# relogioContador.net
KiCad netlist of a schematic drawn in EAGLE
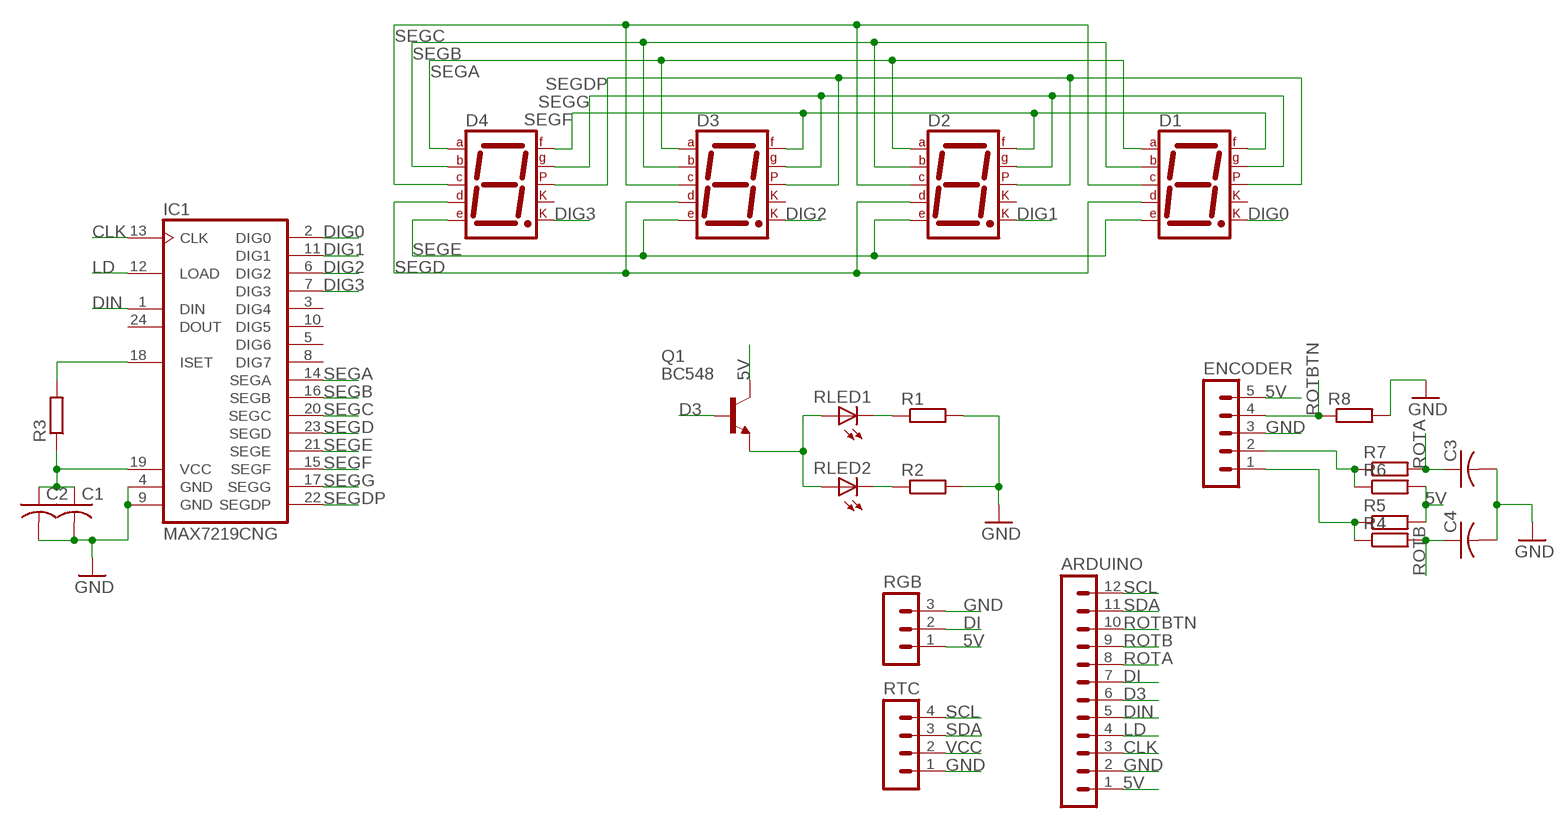
[diagram p0: schematic, sheet 1]

(export (version "E")
  (design (tool "Eeschema 10.0.6"))
  (components
    (comp (ref "ARDUINO")
      (value "MA12-1")
      (footprint "eagle-import:MA12-1")
      (libsource (lib "eagle-import") (part "MA12-1"))
    )
    (comp (ref "C1")
      (value "C-US050-025X075")
      (footprint "eagle-import:C050-025X075")
      (libsource (lib "eagle-import") (part "C-US050-025X075"))
    )
    (comp (ref "C2")
      (value "C-US050-025X075")
      (footprint "eagle-import:C050-025X075")
      (libsource (lib "eagle-import") (part "C-US050-025X075"))
    )
    (comp (ref "C3")
      (value "C-US050-025X075")
      (footprint "eagle-import:C050-025X075")
      (libsource (lib "eagle-import") (part "C-US050-025X075"))
    )
    (comp (ref "C4")
      (value "C-US050-025X075")
      (footprint "eagle-import:C050-025X075")
      (libsource (lib "eagle-import") (part "C-US050-025X075"))
    )
    (comp (ref "D1")
      (value "7SEG-CK")
      (footprint "eagle-import:7SEG-13")
      (libsource (lib "eagle-import") (part "7SEG-CK"))
    )
    (comp (ref "D2")
      (value "7SEG-CK")
      (footprint "eagle-import:7SEG-13")
      (libsource (lib "eagle-import") (part "7SEG-CK"))
    )
    (comp (ref "D3")
      (value "7SEG-CK")
      (footprint "eagle-import:7SEG-13")
      (libsource (lib "eagle-import") (part "7SEG-CK"))
    )
    (comp (ref "D4")
      (value "7SEG-CK")
      (footprint "eagle-import:7SEG-13")
      (libsource (lib "eagle-import") (part "7SEG-CK"))
    )
    (comp (ref "ENCODER")
      (value "MA05-1")
      (footprint "eagle-import:MA05-1")
      (libsource (lib "eagle-import") (part "MA05-1"))
    )
    (comp (ref "IC1")
      (value "MAX7219CNG")
      (footprint "eagle-import:DIL24-3")
      (fields (field (name "MF") "MAXIM"))
      (libsource (lib "eagle-import") (part "MAX7219CNG"))
    )
    (comp (ref "Q1")
      (value "BC548")
      (footprint "eagle-import:TO92-EBC")
      (libsource (lib "eagle-import") (part "BC548"))
    )
    (comp (ref "R1")
      (value "R-EU_0411/15")
      (footprint "eagle-import:0411_15")
      (libsource (lib "eagle-import") (part "R-EU_0411/15"))
    )
    (comp (ref "R2")
      (value "R-EU_0411/15")
      (footprint "eagle-import:0411_15")
      (libsource (lib "eagle-import") (part "R-EU_0411/15"))
    )
    (comp (ref "R3")
      (value "R-EU_0411/15")
      (footprint "eagle-import:0411_15")
      (libsource (lib "eagle-import") (part "R-EU_0411/15"))
    )
    (comp (ref "R4")
      (value "R-EU_0411/15")
      (footprint "eagle-import:0411_15")
      (libsource (lib "eagle-import") (part "R-EU_0411/15"))
    )
    (comp (ref "R5")
      (value "R-EU_0411/15")
      (footprint "eagle-import:0411_15")
      (libsource (lib "eagle-import") (part "R-EU_0411/15"))
    )
    (comp (ref "R6")
      (value "R-EU_0411/15")
      (footprint "eagle-import:0411_15")
      (libsource (lib "eagle-import") (part "R-EU_0411/15"))
    )
    (comp (ref "R7")
      (value "R-EU_0411/15")
      (footprint "eagle-import:0411_15")
      (libsource (lib "eagle-import") (part "R-EU_0411/15"))
    )
    (comp (ref "R8")
      (value "R-EU_0411/15")
      (footprint "eagle-import:0411_15")
      (libsource (lib "eagle-import") (part "R-EU_0411/15"))
    )
    (comp (ref "RGB")
      (value "MA03-1")
      (footprint "eagle-import:MA03-1")
      (libsource (lib "eagle-import") (part "MA03-1"))
    )
    (comp (ref "RLED1")
      (value "LED3MM")
      (footprint "eagle-import:LED3MM")
      (libsource (lib "eagle-import") (part "LED3MM"))
    )
    (comp (ref "RLED2")
      (value "LED3MM")
      (footprint "eagle-import:LED3MM")
      (libsource (lib "eagle-import") (part "LED3MM"))
    )
    (comp (ref "RTC")
      (value "MA04-1")
      (footprint "eagle-import:MA04-1")
      (libsource (lib "eagle-import") (part "MA04-1"))
    )
  )
  (nets
    (net (code "1") (name "/5V") (class "Default")
      (node (ref "ARDUINO") (pin "1") (pinfunction "1_1") (pintype "passive"))
      (node (ref "ENCODER") (pin "5") (pinfunction "5_5") (pintype "passive"))
      (node (ref "Q1") (pin "C") (pinfunction "C_C") (pintype "passive"))
      (node (ref "R5") (pin "2") (pinfunction "2_2") (pintype "passive"))
      (node (ref "R6") (pin "2") (pinfunction "2_2") (pintype "passive"))
      (node (ref "RGB") (pin "1") (pinfunction "1_1") (pintype "passive"))
    )
    (net (code "2") (name "/CLK") (class "Default")
      (node (ref "ARDUINO") (pin "3") (pinfunction "3_3") (pintype "passive"))
      (node (ref "IC1") (pin "13") (pinfunction "CLK_13") (pintype "input"))
    )
    (net (code "3") (name "/D3") (class "Default")
      (node (ref "ARDUINO") (pin "6") (pinfunction "6_6") (pintype "passive"))
      (node (ref "Q1") (pin "B") (pinfunction "B_B") (pintype "passive"))
    )
    (net (code "4") (name "/DI") (class "Default")
      (node (ref "ARDUINO") (pin "7") (pinfunction "7_7") (pintype "passive"))
      (node (ref "RGB") (pin "2") (pinfunction "2_2") (pintype "passive"))
    )
    (net (code "5") (name "/DIG0") (class "Default")
      (node (ref "D1") (pin "8") (pinfunction "CK2_8") (pintype "passive"))
      (node (ref "IC1") (pin "2") (pinfunction "DIG0_2") (pintype "output"))
    )
    (net (code "6") (name "/DIG1") (class "Default")
      (node (ref "D2") (pin "8") (pinfunction "CK2_8") (pintype "passive"))
      (node (ref "IC1") (pin "11") (pinfunction "DIG1_11") (pintype "output"))
    )
    (net (code "7") (name "/DIG2") (class "Default")
      (node (ref "D3") (pin "8") (pinfunction "CK2_8") (pintype "passive"))
      (node (ref "IC1") (pin "6") (pinfunction "DIG2_6") (pintype "output"))
    )
    (net (code "8") (name "/DIG3") (class "Default")
      (node (ref "D4") (pin "8") (pinfunction "CK2_8") (pintype "passive"))
      (node (ref "IC1") (pin "7") (pinfunction "DIG3_7") (pintype "output"))
    )
    (net (code "9") (name "/DIN") (class "Default")
      (node (ref "ARDUINO") (pin "5") (pinfunction "5_5") (pintype "passive"))
      (node (ref "IC1") (pin "1") (pinfunction "DIN_1") (pintype "input"))
    )
    (net (code "10") (name "/LD") (class "Default")
      (node (ref "ARDUINO") (pin "4") (pinfunction "4_4") (pintype "passive"))
      (node (ref "IC1") (pin "12") (pinfunction "LOAD_12") (pintype "input"))
    )
    (net (code "11") (name "/ROTA") (class "Default")
      (node (ref "ARDUINO") (pin "8") (pinfunction "8_8") (pintype "passive"))
      (node (ref "C3") (pin "1") (pinfunction "1_1") (pintype "passive"))
      (node (ref "R7") (pin "2") (pinfunction "2_2") (pintype "passive"))
    )
    (net (code "12") (name "/ROTB") (class "Default")
      (node (ref "ARDUINO") (pin "9") (pinfunction "9_9") (pintype "passive"))
      (node (ref "C4") (pin "1") (pinfunction "1_1") (pintype "passive"))
      (node (ref "R4") (pin "2") (pinfunction "2_2") (pintype "passive"))
    )
    (net (code "13") (name "/ROTBTN") (class "Default")
      (node (ref "ARDUINO") (pin "10") (pinfunction "10_10") (pintype "passive"))
      (node (ref "ENCODER") (pin "4") (pinfunction "4_4") (pintype "passive"))
      (node (ref "R8") (pin "1") (pinfunction "1_1") (pintype "passive"))
    )
    (net (code "14") (name "/SCL") (class "Default")
      (node (ref "ARDUINO") (pin "12") (pinfunction "12_12") (pintype "passive"))
      (node (ref "RTC") (pin "4") (pinfunction "4_4") (pintype "passive"))
    )
    (net (code "15") (name "/SDA") (class "Default")
      (node (ref "ARDUINO") (pin "11") (pinfunction "11_11") (pintype "passive"))
      (node (ref "RTC") (pin "3") (pinfunction "3_3") (pintype "passive"))
    )
    (net (code "16") (name "/SEGA") (class "Default")
      (node (ref "D1") (pin "7") (pinfunction "A_7") (pintype "passive"))
      (node (ref "D2") (pin "7") (pinfunction "A_7") (pintype "passive"))
      (node (ref "D3") (pin "7") (pinfunction "A_7") (pintype "passive"))
      (node (ref "D4") (pin "7") (pinfunction "A_7") (pintype "passive"))
      (node (ref "IC1") (pin "14") (pinfunction "SEGA_14") (pintype "output"))
    )
    (net (code "17") (name "/SEGB") (class "Default")
      (node (ref "D1") (pin "6") (pinfunction "B_6") (pintype "passive"))
      (node (ref "D2") (pin "6") (pinfunction "B_6") (pintype "passive"))
      (node (ref "D3") (pin "6") (pinfunction "B_6") (pintype "passive"))
      (node (ref "D4") (pin "6") (pinfunction "B_6") (pintype "passive"))
      (node (ref "IC1") (pin "16") (pinfunction "SEGB_16") (pintype "output"))
    )
    (net (code "18") (name "/SEGC") (class "Default")
      (node (ref "D1") (pin "4") (pinfunction "C_4") (pintype "passive"))
      (node (ref "D2") (pin "4") (pinfunction "C_4") (pintype "passive"))
      (node (ref "D3") (pin "4") (pinfunction "C_4") (pintype "passive"))
      (node (ref "D4") (pin "4") (pinfunction "C_4") (pintype "passive"))
      (node (ref "IC1") (pin "20") (pinfunction "SEGC_20") (pintype "output"))
    )
    (net (code "19") (name "/SEGD") (class "Default")
      (node (ref "D1") (pin "2") (pinfunction "D_2") (pintype "passive"))
      (node (ref "D2") (pin "2") (pinfunction "D_2") (pintype "passive"))
      (node (ref "D3") (pin "2") (pinfunction "D_2") (pintype "passive"))
      (node (ref "D4") (pin "2") (pinfunction "D_2") (pintype "passive"))
      (node (ref "IC1") (pin "23") (pinfunction "SEGD_23") (pintype "output"))
    )
    (net (code "20") (name "/SEGDP") (class "Default")
      (node (ref "D1") (pin "5") (pinfunction "DP_5") (pintype "passive"))
      (node (ref "D2") (pin "5") (pinfunction "DP_5") (pintype "passive"))
      (node (ref "D3") (pin "5") (pinfunction "DP_5") (pintype "passive"))
      (node (ref "D4") (pin "5") (pinfunction "DP_5") (pintype "passive"))
      (node (ref "IC1") (pin "22") (pinfunction "SEGDP_22") (pintype "output"))
    )
    (net (code "21") (name "/SEGE") (class "Default")
      (node (ref "D1") (pin "1") (pinfunction "E_1") (pintype "passive"))
      (node (ref "D2") (pin "1") (pinfunction "E_1") (pintype "passive"))
      (node (ref "D3") (pin "1") (pinfunction "E_1") (pintype "passive"))
      (node (ref "D4") (pin "1") (pinfunction "E_1") (pintype "passive"))
      (node (ref "IC1") (pin "21") (pinfunction "SEGE_21") (pintype "output"))
    )
    (net (code "22") (name "/SEGF") (class "Default")
      (node (ref "D1") (pin "9") (pinfunction "F_9") (pintype "passive"))
      (node (ref "D2") (pin "9") (pinfunction "F_9") (pintype "passive"))
      (node (ref "D3") (pin "9") (pinfunction "F_9") (pintype "passive"))
      (node (ref "D4") (pin "9") (pinfunction "F_9") (pintype "passive"))
      (node (ref "IC1") (pin "15") (pinfunction "SEGF_15") (pintype "output"))
    )
    (net (code "23") (name "/SEGG") (class "Default")
      (node (ref "D1") (pin "10") (pinfunction "G_10") (pintype "passive"))
      (node (ref "D2") (pin "10") (pinfunction "G_10") (pintype "passive"))
      (node (ref "D3") (pin "10") (pinfunction "G_10") (pintype "passive"))
      (node (ref "D4") (pin "10") (pinfunction "G_10") (pintype "passive"))
      (node (ref "IC1") (pin "17") (pinfunction "SEGG_17") (pintype "output"))
    )
    (net (code "24") (name "/VCC") (class "Default")
      (node (ref "RTC") (pin "2") (pinfunction "2_2") (pintype "passive"))
    )
    (net (code "25") (name "GND") (class "Default")
      (node (ref "ARDUINO") (pin "2") (pinfunction "2_2") (pintype "passive"))
      (node (ref "C1") (pin "2") (pinfunction "2_2") (pintype "passive"))
      (node (ref "C2") (pin "2") (pinfunction "2_2") (pintype "passive"))
      (node (ref "C3") (pin "2") (pinfunction "2_2") (pintype "passive"))
      (node (ref "C4") (pin "2") (pinfunction "2_2") (pintype "passive"))
      (node (ref "ENCODER") (pin "3") (pinfunction "3_3") (pintype "passive"))
      (node (ref "IC1") (pin "4") (pinfunction "GND_4") (pintype "power_in"))
      (node (ref "IC1") (pin "9") (pinfunction "GND_9") (pintype "power_in"))
      (node (ref "R1") (pin "2") (pinfunction "2_2") (pintype "passive"))
      (node (ref "R2") (pin "2") (pinfunction "2_2") (pintype "passive"))
      (node (ref "R8") (pin "2") (pinfunction "2_2") (pintype "passive"))
      (node (ref "RGB") (pin "3") (pinfunction "3_3") (pintype "passive"))
      (node (ref "RTC") (pin "1") (pinfunction "1_1") (pintype "passive"))
    )
    (net (code "26") (name "Net-(ENCODER-Pad1)") (class "Default")
      (node (ref "ENCODER") (pin "1") (pinfunction "1_1") (pintype "passive"))
      (node (ref "R4") (pin "1") (pinfunction "1_1") (pintype "passive"))
      (node (ref "R5") (pin "1") (pinfunction "1_1") (pintype "passive"))
    )
    (net (code "27") (name "Net-(ENCODER-Pad2)") (class "Default")
      (node (ref "ENCODER") (pin "2") (pinfunction "2_2") (pintype "passive"))
      (node (ref "R6") (pin "1") (pinfunction "1_1") (pintype "passive"))
      (node (ref "R7") (pin "1") (pinfunction "1_1") (pintype "passive"))
    )
    (net (code "28") (name "Net-(IC1-ISET)") (class "Default")
      (node (ref "IC1") (pin "18") (pinfunction "ISET_18") (pintype "input"))
      (node (ref "R3") (pin "2") (pinfunction "2_2") (pintype "passive"))
    )
    (net (code "29") (name "Net-(IC1-VCC)") (class "Default")
      (node (ref "C1") (pin "1") (pinfunction "1_1") (pintype "passive"))
      (node (ref "C2") (pin "1") (pinfunction "1_1") (pintype "passive"))
      (node (ref "IC1") (pin "19") (pinfunction "VCC_19") (pintype "power_in"))
      (node (ref "R3") (pin "1") (pinfunction "1_1") (pintype "passive"))
    )
    (net (code "30") (name "Net-(Q1-PadE)") (class "Default")
      (node (ref "Q1") (pin "E") (pinfunction "E_E") (pintype "passive"))
      (node (ref "RLED1") (pin "A") (pinfunction "A_A") (pintype "passive"))
      (node (ref "RLED2") (pin "A") (pinfunction "A_A") (pintype "passive"))
    )
    (net (code "31") (name "Net-(RLED1-C)") (class "Default")
      (node (ref "R1") (pin "1") (pinfunction "1_1") (pintype "passive"))
      (node (ref "RLED1") (pin "K") (pinfunction "C_K") (pintype "passive"))
    )
    (net (code "32") (name "Net-(RLED2-C)") (class "Default")
      (node (ref "R2") (pin "1") (pinfunction "1_1") (pintype "passive"))
      (node (ref "RLED2") (pin "K") (pinfunction "C_K") (pintype "passive"))
    )
    (net (code "33") (name "unconnected-(D1-CK1-Pad3)") (class "Default")
      (node (ref "D1") (pin "3") (pinfunction "CK1_3") (pintype "passive"))
    )
    (net (code "34") (name "unconnected-(D2-CK1-Pad3)") (class "Default")
      (node (ref "D2") (pin "3") (pinfunction "CK1_3") (pintype "passive"))
    )
    (net (code "35") (name "unconnected-(D3-CK1-Pad3)") (class "Default")
      (node (ref "D3") (pin "3") (pinfunction "CK1_3") (pintype "passive"))
    )
    (net (code "36") (name "unconnected-(D4-CK1-Pad3)") (class "Default")
      (node (ref "D4") (pin "3") (pinfunction "CK1_3") (pintype "passive"))
    )
    (net (code "37") (name "unconnected-(IC1-DIG4-Pad3)") (class "Default")
      (node (ref "IC1") (pin "3") (pinfunction "DIG4_3") (pintype "output"))
    )
    (net (code "38") (name "unconnected-(IC1-DIG5-Pad10)") (class "Default")
      (node (ref "IC1") (pin "10") (pinfunction "DIG5_10") (pintype "output"))
    )
    (net (code "39") (name "unconnected-(IC1-DIG6-Pad5)") (class "Default")
      (node (ref "IC1") (pin "5") (pinfunction "DIG6_5") (pintype "output"))
    )
    (net (code "40") (name "unconnected-(IC1-DIG7-Pad8)") (class "Default")
      (node (ref "IC1") (pin "8") (pinfunction "DIG7_8") (pintype "output"))
    )
    (net (code "41") (name "unconnected-(IC1-DOUT-Pad24)") (class "Default")
      (node (ref "IC1") (pin "24") (pinfunction "DOUT_24") (pintype "output"))
    )
  )
)
